# mistral_powertrain_breakout0.net
KiCad netlist of a schematic drawn in EAGLE
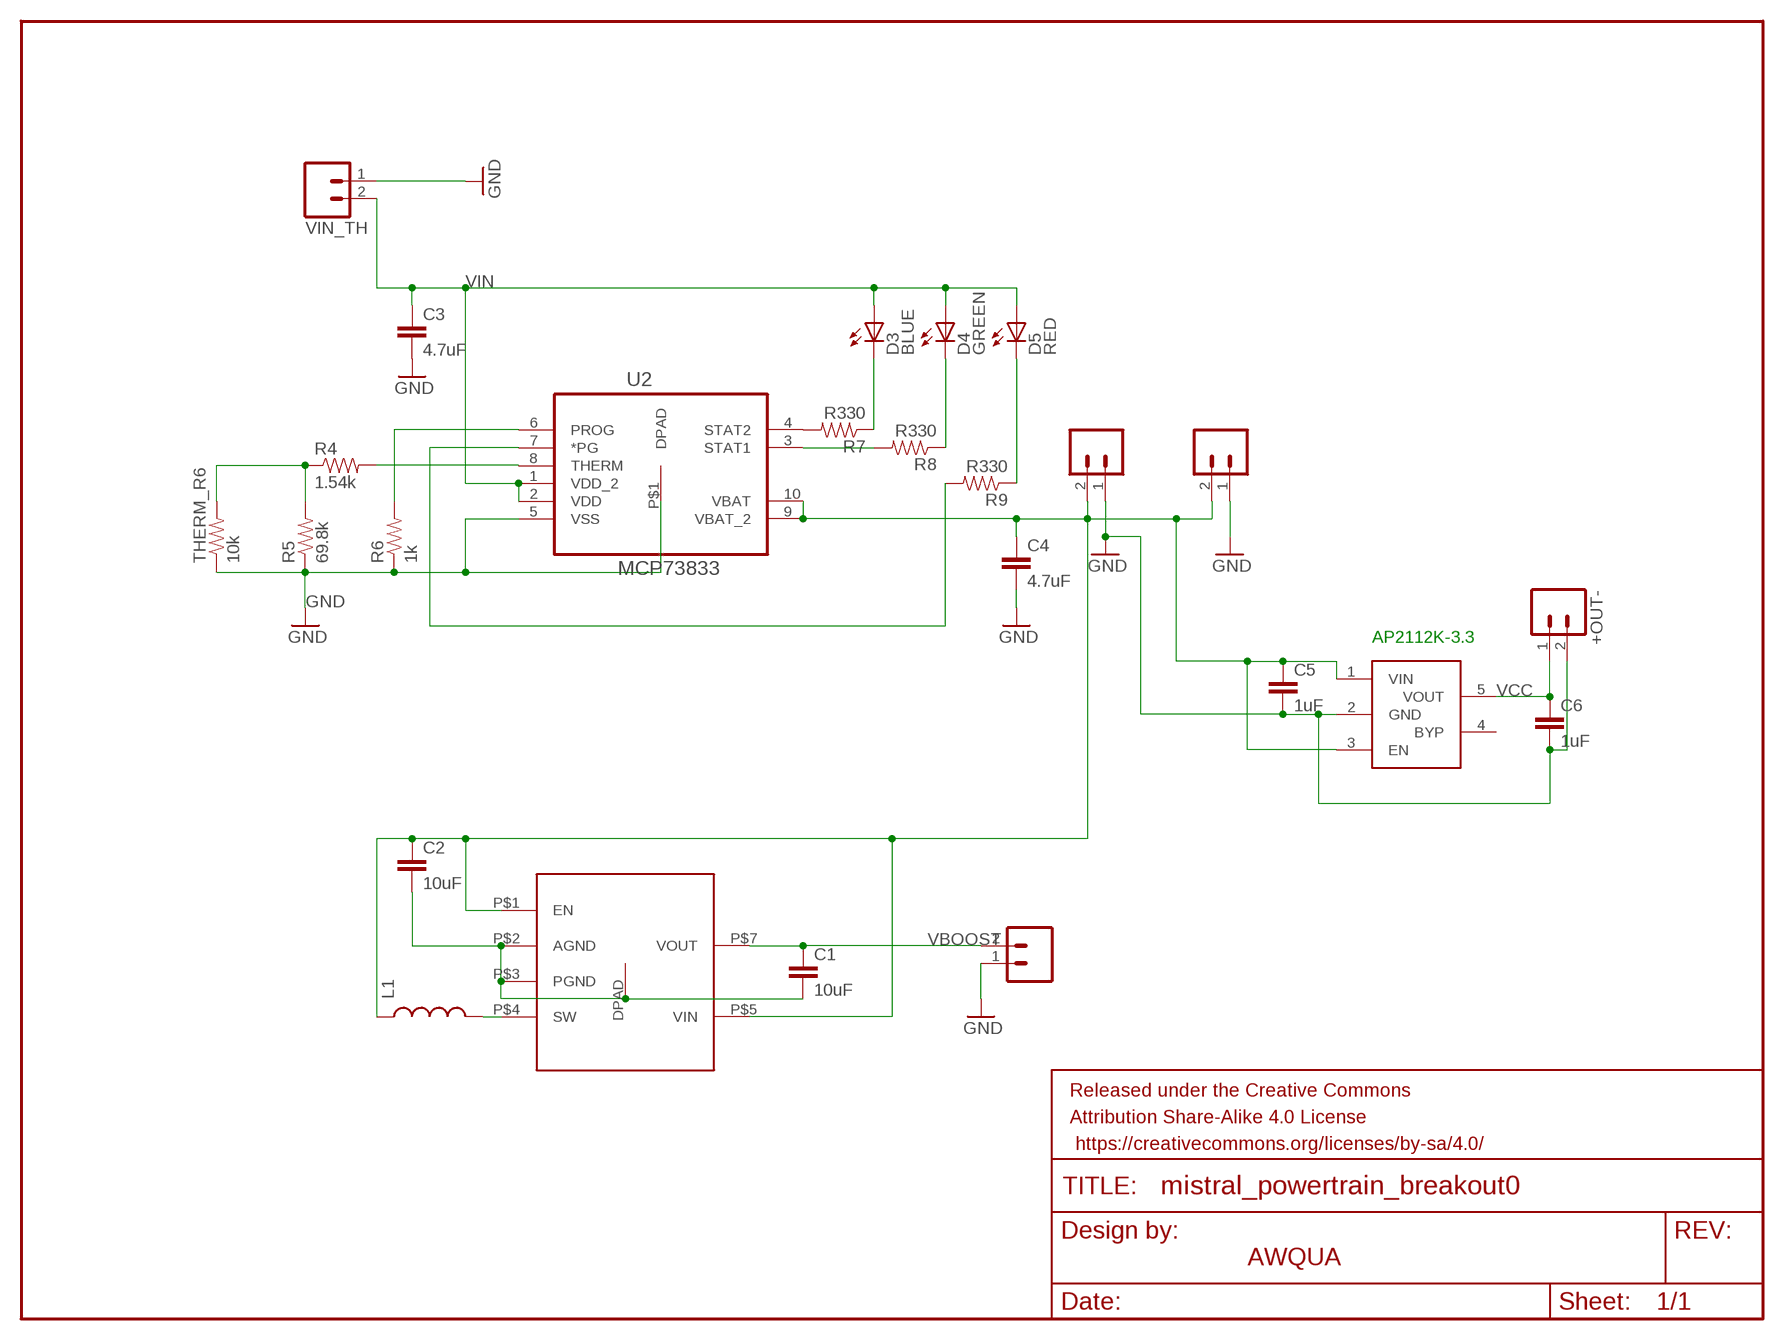
[diagram p0: schematic, sheet 1]

(export (version "E")
  (design (tool "Eeschema 10.0.6"))
  (components
    (comp (ref "+OUT-")
      (value "M02PTH")
      (footprint "eagle-import:1X02")
      (libsource (lib "eagle-import") (part "SparkFun-Connectors_M02PTH"))
    )
    (comp (ref "C1")
      (value "10uF")
      (footprint "eagle-import:0402-CAP")
      (libsource (lib "eagle-import") (part "CAP0402-CAP"))
    )
    (comp (ref "C2")
      (value "10uF")
      (footprint "eagle-import:0402-CAP")
      (libsource (lib "eagle-import") (part "CAP0402-CAP"))
    )
    (comp (ref "C3")
      (value "4.7uF")
      (footprint "eagle-import:0402-CAP")
      (libsource (lib "eagle-import") (part "CAP0402-CAP"))
    )
    (comp (ref "C4")
      (value "4.7uF")
      (footprint "eagle-import:0402-CAP")
      (libsource (lib "eagle-import") (part "CAP0402-CAP"))
    )
    (comp (ref "C5")
      (value "1uF")
      (footprint "eagle-import:0603-CAP")
      (libsource (lib "eagle-import") (part "SparkFun-Passives_CAP0603-CAP"))
    )
    (comp (ref "C6")
      (value "1uF")
      (footprint "eagle-import:0603-CAP")
      (libsource (lib "eagle-import") (part "SparkFun-Passives_CAP0603-CAP"))
    )
    (comp (ref "D3")
      (value "BLUE")
      (footprint "eagle-import:LED-0603")
      (libsource (lib "eagle-import") (part "LED0603"))
    )
    (comp (ref "D4")
      (value "GREEN")
      (footprint "eagle-import:LED-0603")
      (libsource (lib "eagle-import") (part "LED0603"))
    )
    (comp (ref "D5")
      (value "RED")
      (footprint "eagle-import:LED-0603")
      (libsource (lib "eagle-import") (part "LED0603"))
    )
    (comp (ref "FRAME1")
      (value "FRAME-LETTER")
      (footprint "eagle-import:CREATIVE_COMMONS")
      (libsource (lib "eagle-import") (part "FRAME-LETTER"))
    )
    (comp (ref "JMP")
      (value "M02PTH")
      (footprint "eagle-import:1X02")
      (libsource (lib "eagle-import") (part "M02PTH"))
    )
    (comp (ref "JMP1")
      (value "M02PTH")
      (footprint "eagle-import:1X02")
      (libsource (lib "eagle-import") (part "M02PTH"))
    )
    (comp (ref "JP7")
      (value "LiPo Battery")
      (footprint "eagle-import:JST-2-SMD")
      (libsource (lib "eagle-import") (part "M02-JST-2MM-SMT"))
    )
    (comp (ref "L1")
      (value "INDUCTOR0805")
      (footprint "eagle-import:0805")
      (libsource (lib "eagle-import") (part "INDUCTOR0805"))
    )
    (comp (ref "R4")
      (value "1.54k")
      (footprint "eagle-import:0402-RES")
      (libsource (lib "eagle-import") (part "RESISTOR0402-RES"))
    )
    (comp (ref "R5")
      (value "69.8k")
      (footprint "eagle-import:0402-RES")
      (libsource (lib "eagle-import") (part "RESISTOR0402-RES"))
    )
    (comp (ref "R6")
      (value "1k")
      (footprint "eagle-import:0402-RES")
      (libsource (lib "eagle-import") (part "RESISTOR0402-RES"))
    )
    (comp (ref "R7")
      (value "R330")
      (footprint "eagle-import:0402-RES")
      (libsource (lib "eagle-import") (part "RESISTOR0402-RES"))
    )
    (comp (ref "R8")
      (value "R330")
      (footprint "eagle-import:0402-RES")
      (libsource (lib "eagle-import") (part "RESISTOR0402-RES"))
    )
    (comp (ref "R9")
      (value "R330")
      (footprint "eagle-import:0402-RES")
      (libsource (lib "eagle-import") (part "RESISTOR0402-RES"))
    )
    (comp (ref "THERM_R6")
      (value "10k")
      (footprint "eagle-import:0402-RES")
      (libsource (lib "eagle-import") (part "RESISTOR0402-RES"))
    )
    (comp (ref "U$1")
      (value "DIO6605B")
      (footprint "eagle-import:DIO6605B")
      (libsource (lib "eagle-import") (part "DIO6605B"))
    )
    (comp (ref "U$2")
      (value "LP2985")
      (footprint "eagle-import:LP2985")
      (libsource (lib "eagle-import") (part "LP2985"))
    )
    (comp (ref "U2")
      (value "MCP73833")
      (footprint "eagle-import:SOP50P490X110-10N")
      (fields (field (name "MF") "Microchip") (field (name "MP") "MCP73833-GPI/UN"))
      (libsource (lib "eagle-import") (part "MCP73833-GPI/UN"))
    )
    (comp (ref "VIN_TH")
      (value "M02PTH")
      (footprint "eagle-import:1X02")
      (libsource (lib "eagle-import") (part "SparkFun-Connectors_M02PTH"))
    )
  )
  (nets
    (net (code "1") (name "/VBOOST") (class "Default")
      (node (ref "C1") (pin "1") (pinfunction "1_1") (pintype "passive"))
      (node (ref "JMP1") (pin "2") (pinfunction "2_2") (pintype "passive"))
      (node (ref "U$1") (pin "P$7") (pinfunction "VOUT_P$7") (pintype "bidirectional"))
    )
    (net (code "2") (name "/VCC") (class "Default")
      (node (ref "+OUT-") (pin "1") (pinfunction "1_1") (pintype "passive"))
      (node (ref "C6") (pin "1") (pinfunction "1_1") (pintype "passive"))
      (node (ref "U$2") (pin "5") (pinfunction "VOUT_5") (pintype "bidirectional"))
    )
    (net (code "3") (name "/VIN") (class "Default")
      (node (ref "C3") (pin "1") (pinfunction "1_1") (pintype "passive"))
      (node (ref "D3") (pin "A") (pinfunction "A_A") (pintype "passive"))
      (node (ref "D4") (pin "A") (pinfunction "A_A") (pintype "passive"))
      (node (ref "D5") (pin "A") (pinfunction "A_A") (pintype "passive"))
      (node (ref "U2") (pin "1") (pinfunction "VDD_2_1") (pintype "power_in"))
      (node (ref "U2") (pin "2") (pinfunction "VDD_2") (pintype "power_in"))
      (node (ref "VIN_TH") (pin "2") (pinfunction "2_2") (pintype "passive"))
    )
    (net (code "4") (name "GND") (class "Default")
      (node (ref "+OUT-") (pin "2") (pinfunction "2_2") (pintype "passive"))
      (node (ref "C3") (pin "2") (pinfunction "2_2") (pintype "passive"))
      (node (ref "C4") (pin "2") (pinfunction "2_2") (pintype "passive"))
      (node (ref "C5") (pin "2") (pinfunction "2_2") (pintype "passive"))
      (node (ref "C6") (pin "2") (pinfunction "2_2") (pintype "passive"))
      (node (ref "JMP") (pin "1") (pinfunction "1_1") (pintype "passive"))
      (node (ref "JMP1") (pin "1") (pinfunction "1_1") (pintype "passive"))
      (node (ref "JP7") (pin "1") (pinfunction "1_1") (pintype "passive"))
      (node (ref "R5") (pin "1") (pinfunction "1_1") (pintype "passive"))
      (node (ref "R6") (pin "1") (pinfunction "1_1") (pintype "passive"))
      (node (ref "THERM_R6") (pin "1") (pinfunction "1_1") (pintype "passive"))
      (node (ref "U$2") (pin "2") (pinfunction "GND_2") (pintype "bidirectional"))
      (node (ref "U2") (pin "5") (pinfunction "VSS_5") (pintype "passive"))
      (node (ref "U2") (pin "P$1") (pinfunction "DPAD_P$1") (pintype "bidirectional"))
      (node (ref "VIN_TH") (pin "1") (pinfunction "1_1") (pintype "passive"))
    )
    (net (code "5") (name "Net-(D3-PadC)") (class "Default")
      (node (ref "D3") (pin "C") (pinfunction "C_C") (pintype "passive"))
      (node (ref "R7") (pin "1") (pinfunction "1_1") (pintype "passive"))
    )
    (net (code "6") (name "Net-(D4-PadC)") (class "Default")
      (node (ref "D4") (pin "C") (pinfunction "C_C") (pintype "passive"))
      (node (ref "R8") (pin "1") (pinfunction "1_1") (pintype "passive"))
    )
    (net (code "7") (name "Net-(D5-PadC)") (class "Default")
      (node (ref "D5") (pin "C") (pinfunction "C_C") (pintype "passive"))
      (node (ref "R9") (pin "1") (pinfunction "1_1") (pintype "passive"))
    )
    (net (code "8") (name "Net-(R4-Pad1)") (class "Default")
      (node (ref "R4") (pin "1") (pinfunction "1_1") (pintype "passive"))
      (node (ref "R5") (pin "2") (pinfunction "2_2") (pintype "passive"))
      (node (ref "THERM_R6") (pin "2") (pinfunction "2_2") (pintype "passive"))
    )
    (net (code "9") (name "Net-(U$1-AGND)") (class "Default")
      (node (ref "C1") (pin "2") (pinfunction "2_2") (pintype "passive"))
      (node (ref "C2") (pin "2") (pinfunction "2_2") (pintype "passive"))
      (node (ref "U$1") (pin "DPAD") (pinfunction "DGND_DPAD") (pintype "bidirectional"))
      (node (ref "U$1") (pin "P$2") (pinfunction "AGND_P$2") (pintype "bidirectional"))
      (node (ref "U$1") (pin "P$3") (pinfunction "PGND_P$3") (pintype "bidirectional"))
    )
    (net (code "10") (name "Net-(U$1-EN)") (class "Default")
      (node (ref "C2") (pin "1") (pinfunction "1_1") (pintype "passive"))
      (node (ref "C4") (pin "1") (pinfunction "1_1") (pintype "passive"))
      (node (ref "C5") (pin "1") (pinfunction "1_1") (pintype "passive"))
      (node (ref "JMP") (pin "2") (pinfunction "2_2") (pintype "passive"))
      (node (ref "JP7") (pin "2") (pinfunction "2_2") (pintype "passive"))
      (node (ref "L1") (pin "1") (pinfunction "1_1") (pintype "passive"))
      (node (ref "U$1") (pin "P$1") (pinfunction "EN_P$1") (pintype "bidirectional"))
      (node (ref "U$1") (pin "P$5") (pinfunction "VIN_P$5") (pintype "bidirectional"))
      (node (ref "U$2") (pin "1") (pinfunction "VIN_1") (pintype "bidirectional"))
      (node (ref "U$2") (pin "3") (pinfunction "EN_3") (pintype "bidirectional"))
      (node (ref "U2") (pin "10") (pinfunction "VBAT_10") (pintype "output"))
      (node (ref "U2") (pin "9") (pinfunction "VBAT_2_9") (pintype "output"))
    )
    (net (code "11") (name "Net-(U$1-SW)") (class "Default")
      (node (ref "L1") (pin "2") (pinfunction "2_2") (pintype "passive"))
      (node (ref "U$1") (pin "P$4") (pinfunction "SW_P$4") (pintype "bidirectional"))
    )
    (net (code "12") (name "Net-(U2-*PG)") (class "Default")
      (node (ref "R9") (pin "2") (pinfunction "2_2") (pintype "passive"))
      (node (ref "U2") (pin "7") (pinfunction "*PG_7") (pintype "input"))
    )
    (net (code "13") (name "Net-(U2-PROG)") (class "Default")
      (node (ref "R6") (pin "2") (pinfunction "2_2") (pintype "passive"))
      (node (ref "U2") (pin "6") (pinfunction "PROG_6") (pintype "input"))
    )
    (net (code "14") (name "Net-(U2-STAT1)") (class "Default")
      (node (ref "R8") (pin "2") (pinfunction "2_2") (pintype "passive"))
      (node (ref "U2") (pin "3") (pinfunction "STAT1_3") (pintype "output"))
    )
    (net (code "15") (name "Net-(U2-STAT2)") (class "Default")
      (node (ref "R7") (pin "2") (pinfunction "2_2") (pintype "passive"))
      (node (ref "U2") (pin "4") (pinfunction "STAT2_4") (pintype "output"))
    )
    (net (code "16") (name "Net-(U2-THERM)") (class "Default")
      (node (ref "R4") (pin "2") (pinfunction "2_2") (pintype "passive"))
      (node (ref "U2") (pin "8") (pinfunction "THERM_8") (pintype "input"))
    )
    (net (code "17") (name "unconnected-(U$2-BYP-Pad4)") (class "Default")
      (node (ref "U$2") (pin "4") (pinfunction "BYP_4") (pintype "bidirectional"))
    )
  )
)
